# gigafoc.net
KiCad netlist of a schematic drawn in EAGLE
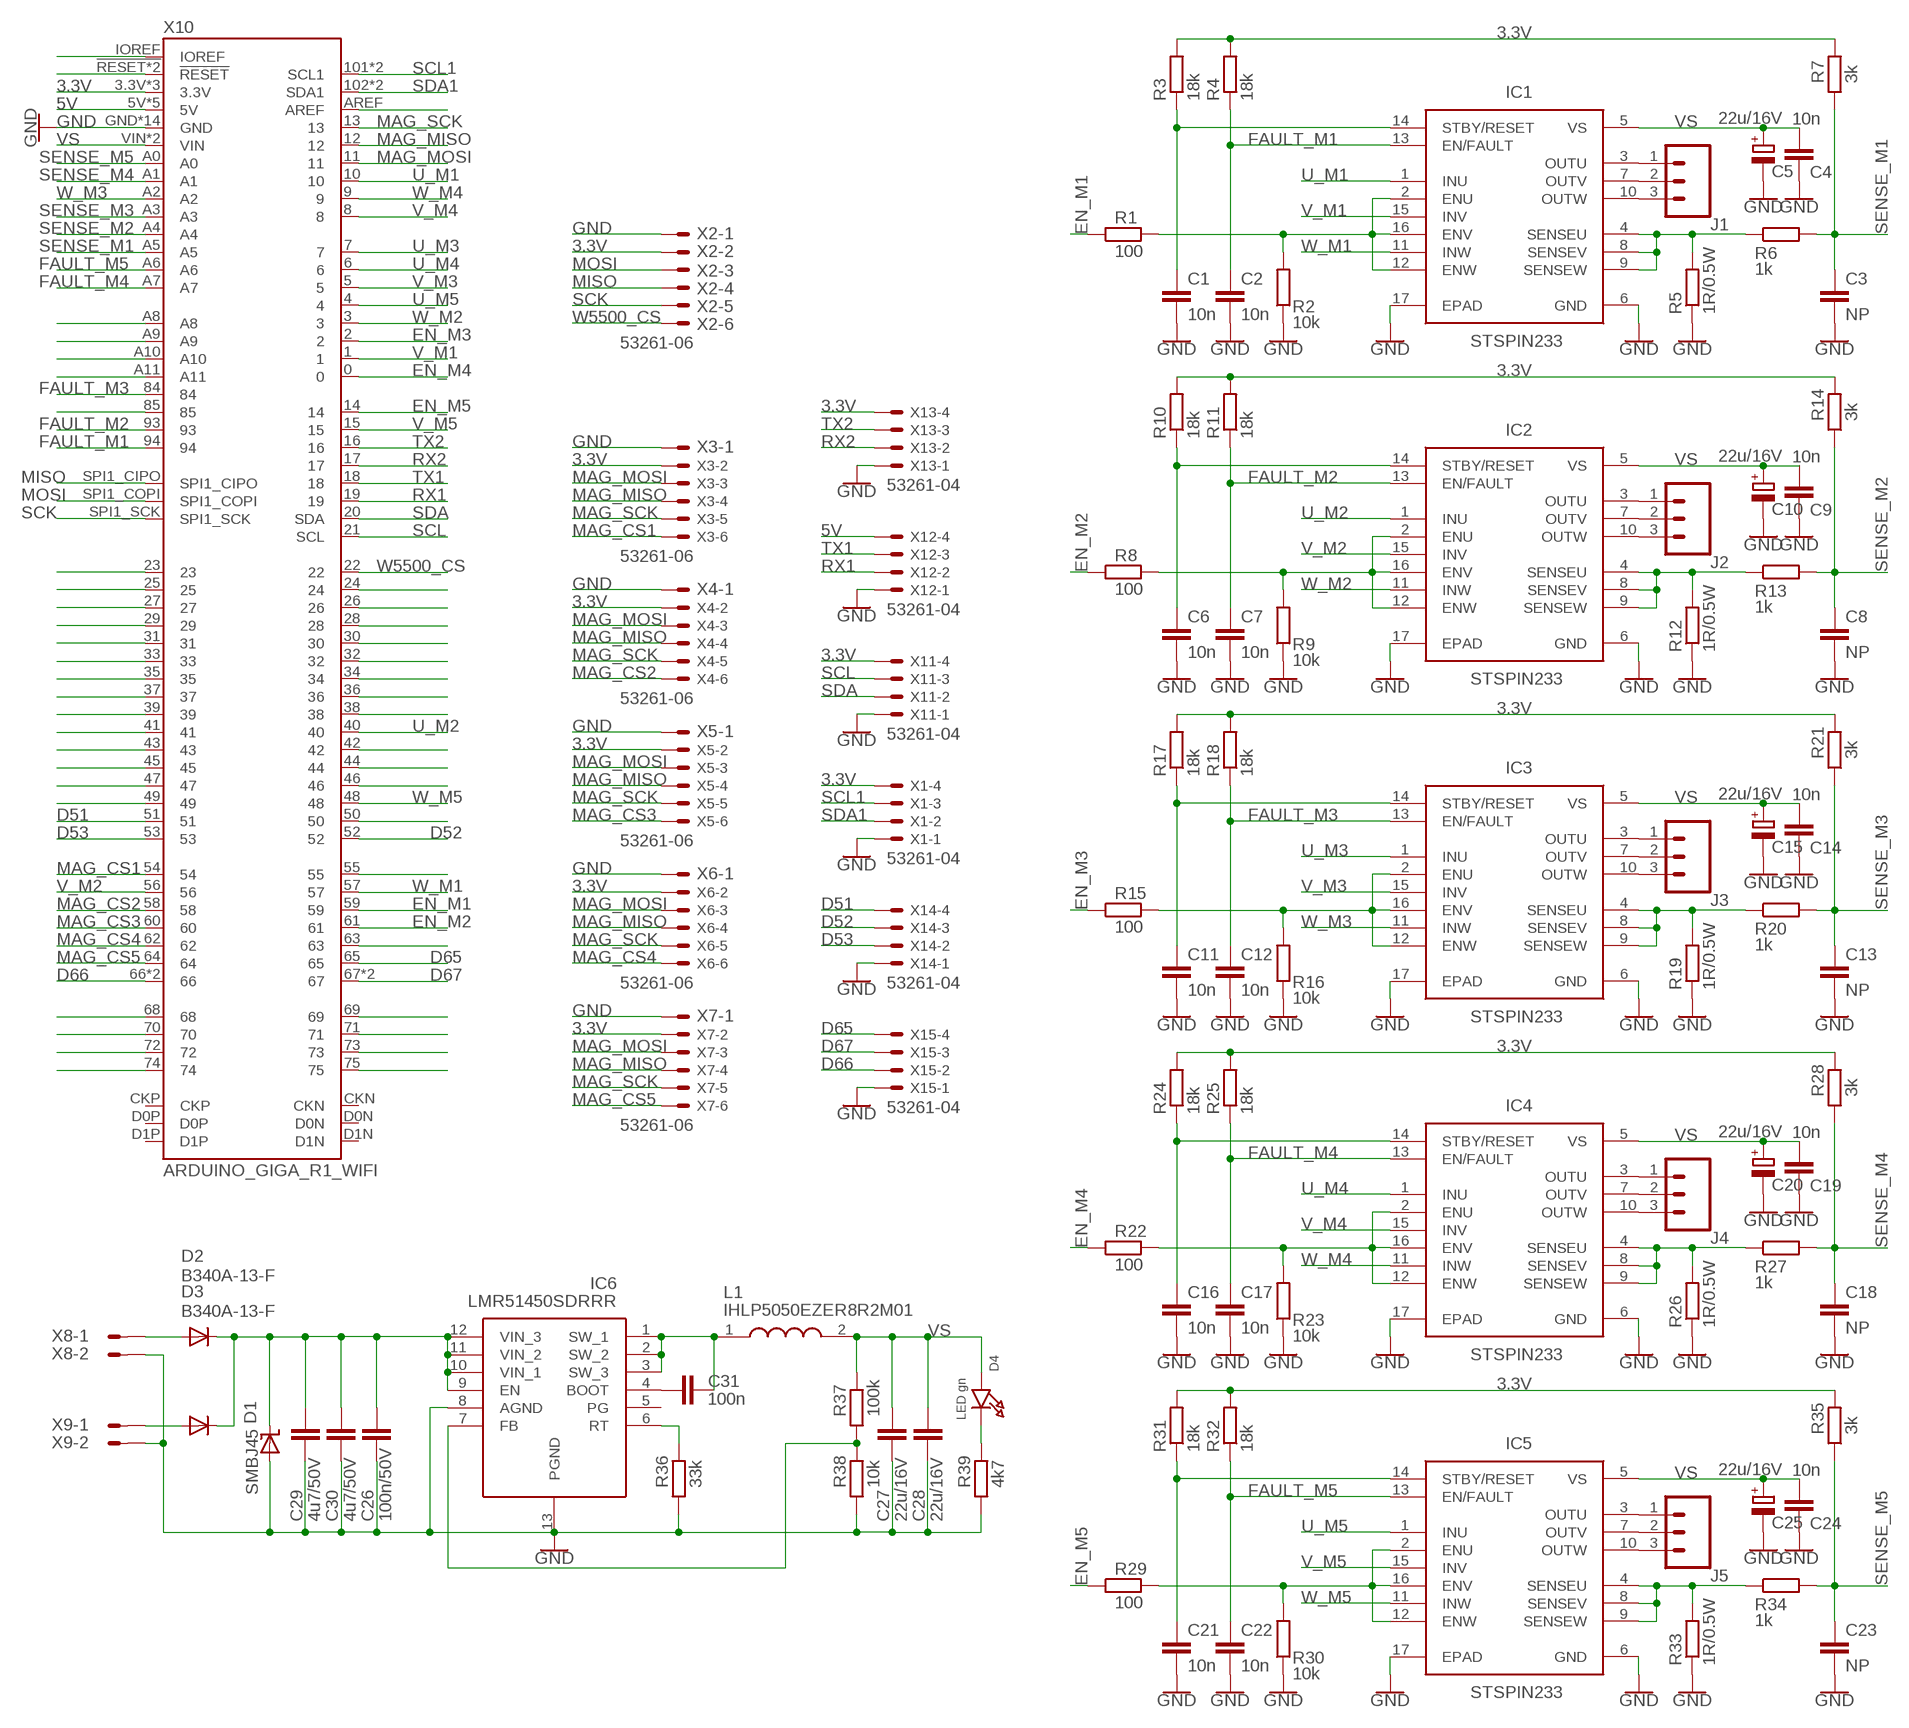
[diagram p0: schematic, sheet 1]

(export (version "E")
  (design (tool "Eeschema 10.0.6"))
  (components
    (comp (ref "C1")
      (value "10n")
      (footprint "eagle-import:C0603")
      (libsource (lib "eagle-import") (part "C-EUC0603"))
    )
    (comp (ref "C2")
      (value "10n")
      (footprint "eagle-import:C0603")
      (libsource (lib "eagle-import") (part "C-EUC0603"))
    )
    (comp (ref "C3")
      (value "NP")
      (footprint "eagle-import:C0603")
      (libsource (lib "eagle-import") (part "C-EUC0603"))
    )
    (comp (ref "C4")
      (value "10n")
      (footprint "eagle-import:C0603")
      (libsource (lib "eagle-import") (part "C-EUC0603"))
    )
    (comp (ref "C5")
      (value "22u/16V")
      (footprint "eagle-import:SMC_B")
      (libsource (lib "eagle-import") (part "CPOL-EUSMCB"))
    )
    (comp (ref "C6")
      (value "10n")
      (footprint "eagle-import:C0603")
      (libsource (lib "eagle-import") (part "C-EUC0603"))
    )
    (comp (ref "C7")
      (value "10n")
      (footprint "eagle-import:C0603")
      (libsource (lib "eagle-import") (part "C-EUC0603"))
    )
    (comp (ref "C8")
      (value "NP")
      (footprint "eagle-import:C0603")
      (libsource (lib "eagle-import") (part "C-EUC0603"))
    )
    (comp (ref "C9")
      (value "10n")
      (footprint "eagle-import:C0603")
      (libsource (lib "eagle-import") (part "C-EUC0603"))
    )
    (comp (ref "C10")
      (value "22u/16V")
      (footprint "eagle-import:SMC_B")
      (libsource (lib "eagle-import") (part "CPOL-EUSMCB"))
    )
    (comp (ref "C11")
      (value "10n")
      (footprint "eagle-import:C0603")
      (libsource (lib "eagle-import") (part "C-EUC0603"))
    )
    (comp (ref "C12")
      (value "10n")
      (footprint "eagle-import:C0603")
      (libsource (lib "eagle-import") (part "C-EUC0603"))
    )
    (comp (ref "C13")
      (value "NP")
      (footprint "eagle-import:C0603")
      (libsource (lib "eagle-import") (part "C-EUC0603"))
    )
    (comp (ref "C14")
      (value "10n")
      (footprint "eagle-import:C0603")
      (libsource (lib "eagle-import") (part "C-EUC0603"))
    )
    (comp (ref "C15")
      (value "22u/16V")
      (footprint "eagle-import:SMC_B")
      (libsource (lib "eagle-import") (part "CPOL-EUSMCB"))
    )
    (comp (ref "C16")
      (value "10n")
      (footprint "eagle-import:C0603")
      (libsource (lib "eagle-import") (part "C-EUC0603"))
    )
    (comp (ref "C17")
      (value "10n")
      (footprint "eagle-import:C0603")
      (libsource (lib "eagle-import") (part "C-EUC0603"))
    )
    (comp (ref "C18")
      (value "NP")
      (footprint "eagle-import:C0603")
      (libsource (lib "eagle-import") (part "C-EUC0603"))
    )
    (comp (ref "C19")
      (value "10n")
      (footprint "eagle-import:C0603")
      (libsource (lib "eagle-import") (part "C-EUC0603"))
    )
    (comp (ref "C20")
      (value "22u/16V")
      (footprint "eagle-import:SMC_B")
      (libsource (lib "eagle-import") (part "CPOL-EUSMCB"))
    )
    (comp (ref "C21")
      (value "10n")
      (footprint "eagle-import:C0603")
      (libsource (lib "eagle-import") (part "C-EUC0603"))
    )
    (comp (ref "C22")
      (value "10n")
      (footprint "eagle-import:C0603")
      (libsource (lib "eagle-import") (part "C-EUC0603"))
    )
    (comp (ref "C23")
      (value "NP")
      (footprint "eagle-import:C0603")
      (libsource (lib "eagle-import") (part "C-EUC0603"))
    )
    (comp (ref "C24")
      (value "10n")
      (footprint "eagle-import:C0603")
      (libsource (lib "eagle-import") (part "C-EUC0603"))
    )
    (comp (ref "C25")
      (value "22u/16V")
      (footprint "eagle-import:SMC_B")
      (libsource (lib "eagle-import") (part "CPOL-EUSMCB"))
    )
    (comp (ref "C26")
      (value "100n/50V")
      (footprint "eagle-import:C0805")
      (libsource (lib "eagle-import") (part "C-EUC0805"))
    )
    (comp (ref "C27")
      (value "22u/16V")
      (footprint "eagle-import:C1210")
      (libsource (lib "eagle-import") (part "C-EUC1210"))
    )
    (comp (ref "C28")
      (value "22u/16V")
      (footprint "eagle-import:C1210")
      (libsource (lib "eagle-import") (part "C-EUC1210"))
    )
    (comp (ref "C29")
      (value "4u7/50V")
      (footprint "eagle-import:C1210K")
      (libsource (lib "eagle-import") (part "C-EUC1210K"))
    )
    (comp (ref "C30")
      (value "4u7/50V")
      (footprint "eagle-import:C1210K")
      (libsource (lib "eagle-import") (part "C-EUC1210K"))
    )
    (comp (ref "C31")
      (value "100n")
      (footprint "eagle-import:C0603")
      (libsource (lib "eagle-import") (part "C-EUC0603"))
    )
    (comp (ref "D1")
      (value "SMBJ45")
      (footprint "eagle-import:SMBJ")
      (libsource (lib "eagle-import") (part "SUPPRESSOR-SMBJ"))
    )
    (comp (ref "D2")
      (value "B340A-13-F")
      (footprint "eagle-import:DO214AC")
      (libsource (lib "eagle-import") (part "DIODE-DO214AC"))
    )
    (comp (ref "D3")
      (value "B340A-13-F")
      (footprint "eagle-import:DO214AC")
      (libsource (lib "eagle-import") (part "DIODE-DO214AC"))
    )
    (comp (ref "D4")
      (value "LED gn")
      (footprint "eagle-import:CHIPLED_0603_NOOUTLINE")
      (libsource (lib "eagle-import") (part "LED0603_NOOUTLINE"))
    )
    (comp (ref "IC1")
      (value "STSPIN233")
      (footprint "eagle-import:QFN50P300X300X100-17N")
      (fields (field (name "MOUSER_PART_NUMBER") "511-STSPIN233"))
      (libsource (lib "eagle-import") (part "STSPIN233"))
    )
    (comp (ref "IC2")
      (value "STSPIN233")
      (footprint "eagle-import:QFN50P300X300X100-17N")
      (fields (field (name "MOUSER_PART_NUMBER") "511-STSPIN233"))
      (libsource (lib "eagle-import") (part "STSPIN233"))
    )
    (comp (ref "IC3")
      (value "STSPIN233")
      (footprint "eagle-import:QFN50P300X300X100-17N")
      (fields (field (name "MOUSER_PART_NUMBER") "511-STSPIN233"))
      (libsource (lib "eagle-import") (part "STSPIN233"))
    )
    (comp (ref "IC4")
      (value "STSPIN233")
      (footprint "eagle-import:QFN50P300X300X100-17N")
      (fields (field (name "MOUSER_PART_NUMBER") "511-STSPIN233"))
      (libsource (lib "eagle-import") (part "STSPIN233"))
    )
    (comp (ref "IC5")
      (value "STSPIN233")
      (footprint "eagle-import:QFN50P300X300X100-17N")
      (fields (field (name "MOUSER_PART_NUMBER") "511-STSPIN233"))
      (libsource (lib "eagle-import") (part "STSPIN233"))
    )
    (comp (ref "IC6")
      (value "LMR51450SDRRR")
      (footprint "eagle-import:SON50P300X300X80-13N")
      (fields (field (name "MOUSER_PART_NUMBER") "595-LMR51450SDRRR"))
      (libsource (lib "eagle-import") (part "LMR51450SDRRR"))
    )
    (comp (ref "J1")
      (value "CONN_03POLAR")
      (footprint "eagle-import:MOLEX-1X3")
      (libsource (lib "eagle-import") (part "CONN_03POLAR"))
    )
    (comp (ref "J2")
      (value "CONN_03POLAR")
      (footprint "eagle-import:MOLEX-1X3")
      (libsource (lib "eagle-import") (part "CONN_03POLAR"))
    )
    (comp (ref "J3")
      (value "CONN_03POLAR")
      (footprint "eagle-import:MOLEX-1X3")
      (libsource (lib "eagle-import") (part "CONN_03POLAR"))
    )
    (comp (ref "J4")
      (value "CONN_03POLAR")
      (footprint "eagle-import:MOLEX-1X3")
      (libsource (lib "eagle-import") (part "CONN_03POLAR"))
    )
    (comp (ref "J5")
      (value "CONN_03POLAR")
      (footprint "eagle-import:MOLEX-1X3")
      (libsource (lib "eagle-import") (part "CONN_03POLAR"))
    )
    (comp (ref "L1")
      (value "IHLP5050EZER8R2M01")
      (footprint "eagle-import:INDPM132129X500N")
      (fields (field (name "MOUSER_PART_NUMBER") "70-IHLP5050EZER8R2M1"))
      (libsource (lib "eagle-import") (part "IHLP5050EZER8R2M01"))
    )
    (comp (ref "R1")
      (value "100")
      (footprint "eagle-import:R0603")
      (libsource (lib "eagle-import") (part "R-EU_R0603"))
    )
    (comp (ref "R2")
      (value "10k")
      (footprint "eagle-import:R0603")
      (libsource (lib "eagle-import") (part "R-EU_R0603"))
    )
    (comp (ref "R3")
      (value "18k")
      (footprint "eagle-import:R0603")
      (libsource (lib "eagle-import") (part "R-EU_R0603"))
    )
    (comp (ref "R4")
      (value "18k")
      (footprint "eagle-import:R0603")
      (libsource (lib "eagle-import") (part "R-EU_R0603"))
    )
    (comp (ref "R5")
      (value "1R/0.5W")
      (footprint "eagle-import:R1206")
      (libsource (lib "eagle-import") (part "R-EU_R1206"))
    )
    (comp (ref "R6")
      (value "1k")
      (footprint "eagle-import:R0603")
      (libsource (lib "eagle-import") (part "R-EU_R0603"))
    )
    (comp (ref "R7")
      (value "3k")
      (footprint "eagle-import:R0603")
      (libsource (lib "eagle-import") (part "R-EU_R0603"))
    )
    (comp (ref "R8")
      (value "100")
      (footprint "eagle-import:R0603")
      (libsource (lib "eagle-import") (part "R-EU_R0603"))
    )
    (comp (ref "R9")
      (value "10k")
      (footprint "eagle-import:R0603")
      (libsource (lib "eagle-import") (part "R-EU_R0603"))
    )
    (comp (ref "R10")
      (value "18k")
      (footprint "eagle-import:R0603")
      (libsource (lib "eagle-import") (part "R-EU_R0603"))
    )
    (comp (ref "R11")
      (value "18k")
      (footprint "eagle-import:R0603")
      (libsource (lib "eagle-import") (part "R-EU_R0603"))
    )
    (comp (ref "R12")
      (value "1R/0.5W")
      (footprint "eagle-import:R1206")
      (libsource (lib "eagle-import") (part "R-EU_R1206"))
    )
    (comp (ref "R13")
      (value "1k")
      (footprint "eagle-import:R0603")
      (libsource (lib "eagle-import") (part "R-EU_R0603"))
    )
    (comp (ref "R14")
      (value "3k")
      (footprint "eagle-import:R0603")
      (libsource (lib "eagle-import") (part "R-EU_R0603"))
    )
    (comp (ref "R15")
      (value "100")
      (footprint "eagle-import:R0603")
      (libsource (lib "eagle-import") (part "R-EU_R0603"))
    )
    (comp (ref "R16")
      (value "10k")
      (footprint "eagle-import:R0603")
      (libsource (lib "eagle-import") (part "R-EU_R0603"))
    )
    (comp (ref "R17")
      (value "18k")
      (footprint "eagle-import:R0603")
      (libsource (lib "eagle-import") (part "R-EU_R0603"))
    )
    (comp (ref "R18")
      (value "18k")
      (footprint "eagle-import:R0603")
      (libsource (lib "eagle-import") (part "R-EU_R0603"))
    )
    (comp (ref "R19")
      (value "1R/0.5W")
      (footprint "eagle-import:R1206")
      (libsource (lib "eagle-import") (part "R-EU_R1206"))
    )
    (comp (ref "R20")
      (value "1k")
      (footprint "eagle-import:R0603")
      (libsource (lib "eagle-import") (part "R-EU_R0603"))
    )
    (comp (ref "R21")
      (value "3k")
      (footprint "eagle-import:R0603")
      (libsource (lib "eagle-import") (part "R-EU_R0603"))
    )
    (comp (ref "R22")
      (value "100")
      (footprint "eagle-import:R0603")
      (libsource (lib "eagle-import") (part "R-EU_R0603"))
    )
    (comp (ref "R23")
      (value "10k")
      (footprint "eagle-import:R0603")
      (libsource (lib "eagle-import") (part "R-EU_R0603"))
    )
    (comp (ref "R24")
      (value "18k")
      (footprint "eagle-import:R0603")
      (libsource (lib "eagle-import") (part "R-EU_R0603"))
    )
    (comp (ref "R25")
      (value "18k")
      (footprint "eagle-import:R0603")
      (libsource (lib "eagle-import") (part "R-EU_R0603"))
    )
    (comp (ref "R26")
      (value "1R/0.5W")
      (footprint "eagle-import:R1206")
      (libsource (lib "eagle-import") (part "R-EU_R1206"))
    )
    (comp (ref "R27")
      (value "1k")
      (footprint "eagle-import:R0603")
      (libsource (lib "eagle-import") (part "R-EU_R0603"))
    )
    (comp (ref "R28")
      (value "3k")
      (footprint "eagle-import:R0603")
      (libsource (lib "eagle-import") (part "R-EU_R0603"))
    )
    (comp (ref "R29")
      (value "100")
      (footprint "eagle-import:R0603")
      (libsource (lib "eagle-import") (part "R-EU_R0603"))
    )
    (comp (ref "R30")
      (value "10k")
      (footprint "eagle-import:R0603")
      (libsource (lib "eagle-import") (part "R-EU_R0603"))
    )
    (comp (ref "R31")
      (value "18k")
      (footprint "eagle-import:R0603")
      (libsource (lib "eagle-import") (part "R-EU_R0603"))
    )
    (comp (ref "R32")
      (value "18k")
      (footprint "eagle-import:R0603")
      (libsource (lib "eagle-import") (part "R-EU_R0603"))
    )
    (comp (ref "R33")
      (value "1R/0.5W")
      (footprint "eagle-import:R1206")
      (libsource (lib "eagle-import") (part "R-EU_R1206"))
    )
    (comp (ref "R34")
      (value "1k")
      (footprint "eagle-import:R0603")
      (libsource (lib "eagle-import") (part "R-EU_R0603"))
    )
    (comp (ref "R35")
      (value "3k")
      (footprint "eagle-import:R0603")
      (libsource (lib "eagle-import") (part "R-EU_R0603"))
    )
    (comp (ref "R36")
      (value "33k")
      (footprint "eagle-import:R0603")
      (libsource (lib "eagle-import") (part "R-EU_R0603"))
    )
    (comp (ref "R37")
      (value "100k")
      (footprint "eagle-import:R0603")
      (libsource (lib "eagle-import") (part "R-EU_R0603"))
    )
    (comp (ref "R38")
      (value "10k")
      (footprint "eagle-import:R0603")
      (libsource (lib "eagle-import") (part "R-EU_R0603"))
    )
    (comp (ref "R39")
      (value "4k7")
      (footprint "eagle-import:R0603")
      (libsource (lib "eagle-import") (part "R-EU_R0603"))
    )
    (comp (ref "X1")
      (value "53261-04")
      (footprint "eagle-import:53261-04")
      (fields (field (name "MF") "MOLEX"))
      (libsource (lib "eagle-import") (part "53?-04261"))
    )
    (comp (ref "X2")
      (value "53261-06")
      (footprint "eagle-import:53261-06")
      (fields (field (name "MF") "MOLEX"))
      (libsource (lib "eagle-import") (part "53?-06261"))
    )
    (comp (ref "X3")
      (value "53261-06")
      (footprint "eagle-import:53261-06")
      (fields (field (name "MF") "MOLEX"))
      (libsource (lib "eagle-import") (part "53?-06261"))
    )
    (comp (ref "X4")
      (value "53261-06")
      (footprint "eagle-import:53261-06")
      (fields (field (name "MF") "MOLEX"))
      (libsource (lib "eagle-import") (part "53?-06261"))
    )
    (comp (ref "X5")
      (value "53261-06")
      (footprint "eagle-import:53261-06")
      (fields (field (name "MF") "MOLEX"))
      (libsource (lib "eagle-import") (part "53?-06261"))
    )
    (comp (ref "X6")
      (value "53261-06")
      (footprint "eagle-import:53261-06")
      (fields (field (name "MF") "MOLEX"))
      (libsource (lib "eagle-import") (part "53?-06261"))
    )
    (comp (ref "X7")
      (value "53261-06")
      (footprint "eagle-import:53261-06")
      (fields (field (name "MF") "MOLEX"))
      (libsource (lib "eagle-import") (part "53?-06261"))
    )
    (comp (ref "X8")
      (value "S02P")
      (footprint "eagle-import:S02P")
      (libsource (lib "eagle-import") (part "S02P"))
    )
    (comp (ref "X9")
      (value "S02P")
      (footprint "eagle-import:S02P")
      (libsource (lib "eagle-import") (part "S02P"))
    )
    (comp (ref "X10")
      (value "ARDUINO_GIGA_R1_WIFI")
      (footprint "eagle-import:ARDUINO_GIGA_NO_SILK")
      (libsource (lib "eagle-import") (part "ARDUINO_GIGA_R1_WIFI"))
    )
    (comp (ref "X11")
      (value "53261-04")
      (footprint "eagle-import:53261-04")
      (fields (field (name "MF") "MOLEX"))
      (libsource (lib "eagle-import") (part "53?-04261"))
    )
    (comp (ref "X12")
      (value "53261-04")
      (footprint "eagle-import:53261-04")
      (fields (field (name "MF") "MOLEX"))
      (libsource (lib "eagle-import") (part "53?-04261"))
    )
    (comp (ref "X13")
      (value "53261-04")
      (footprint "eagle-import:53261-04")
      (fields (field (name "MF") "MOLEX"))
      (libsource (lib "eagle-import") (part "53?-04261"))
    )
    (comp (ref "X14")
      (value "53261-04")
      (footprint "eagle-import:53261-04")
      (fields (field (name "MF") "MOLEX"))
      (libsource (lib "eagle-import") (part "53?-04261"))
    )
    (comp (ref "X15")
      (value "53261-04")
      (footprint "eagle-import:53261-04")
      (fields (field (name "MF") "MOLEX"))
      (libsource (lib "eagle-import") (part "53?-04261"))
    )
  )
  (nets
    (net (code "1") (name "/3.3V") (class "Default")
      (node (ref "R10") (pin "2") (pinfunction "2_2") (pintype "passive"))
      (node (ref "R11") (pin "2") (pinfunction "2_2") (pintype "passive"))
      (node (ref "R14") (pin "2") (pinfunction "2_2") (pintype "passive"))
      (node (ref "R17") (pin "2") (pinfunction "2_2") (pintype "passive"))
      (node (ref "R18") (pin "2") (pinfunction "2_2") (pintype "passive"))
      (node (ref "R21") (pin "2") (pinfunction "2_2") (pintype "passive"))
      (node (ref "R24") (pin "2") (pinfunction "2_2") (pintype "passive"))
      (node (ref "R25") (pin "2") (pinfunction "2_2") (pintype "passive"))
      (node (ref "R28") (pin "2") (pinfunction "2_2") (pintype "passive"))
      (node (ref "R3") (pin "2") (pinfunction "2_2") (pintype "passive"))
      (node (ref "R31") (pin "2") (pinfunction "2_2") (pintype "passive"))
      (node (ref "R32") (pin "2") (pinfunction "2_2") (pintype "passive"))
      (node (ref "R35") (pin "2") (pinfunction "2_2") (pintype "passive"))
      (node (ref "R4") (pin "2") (pinfunction "2_2") (pintype "passive"))
      (node (ref "R7") (pin "2") (pinfunction "2_2") (pintype "passive"))
      (node (ref "X1") (pin "4") (pinfunction "S_4") (pintype "passive"))
      (node (ref "X10") (pin "3.3V") (pinfunction "3.3V_3.3V") (pintype "bidirectional"))
      (node (ref "X10") (pin "3.3V@1") (pinfunction "3.3V_3.3V@1") (pintype "bidirectional"))
      (node (ref "X10") (pin "3.3V@2") (pinfunction "3.3V_3.3V@2") (pintype "bidirectional"))
      (node (ref "X11") (pin "4") (pinfunction "S_4") (pintype "passive"))
      (node (ref "X13") (pin "4") (pinfunction "S_4") (pintype "passive"))
      (node (ref "X2") (pin "2") (pinfunction "S_2") (pintype "passive"))
      (node (ref "X3") (pin "2") (pinfunction "S_2") (pintype "passive"))
      (node (ref "X4") (pin "2") (pinfunction "S_2") (pintype "passive"))
      (node (ref "X5") (pin "2") (pinfunction "S_2") (pintype "passive"))
      (node (ref "X6") (pin "2") (pinfunction "S_2") (pintype "passive"))
      (node (ref "X7") (pin "2") (pinfunction "S_2") (pintype "passive"))
    )
    (net (code "2") (name "/5V") (class "Default")
      (node (ref "X10") (pin "5V") (pinfunction "5V_5V") (pintype "bidirectional"))
      (node (ref "X10") (pin "5V@1") (pinfunction "5V_5V@1") (pintype "bidirectional"))
      (node (ref "X10") (pin "5V@2") (pinfunction "5V_5V@2") (pintype "bidirectional"))
      (node (ref "X10") (pin "5V@3") (pinfunction "5V_5V@3") (pintype "bidirectional"))
      (node (ref "X10") (pin "5V@4") (pinfunction "5V_5V@4") (pintype "bidirectional"))
      (node (ref "X12") (pin "4") (pinfunction "S_4") (pintype "passive"))
    )
    (net (code "3") (name "/D51") (class "Default")
      (node (ref "X10") (pin "51") (pinfunction "51_51") (pintype "bidirectional"))
      (node (ref "X14") (pin "4") (pinfunction "S_4") (pintype "passive"))
    )
    (net (code "4") (name "/D52") (class "Default")
      (node (ref "X10") (pin "52") (pinfunction "52_52") (pintype "bidirectional"))
      (node (ref "X14") (pin "3") (pinfunction "S_3") (pintype "passive"))
    )
    (net (code "5") (name "/D53") (class "Default")
      (node (ref "X10") (pin "53") (pinfunction "53_53") (pintype "bidirectional"))
      (node (ref "X14") (pin "2") (pinfunction "S_2") (pintype "passive"))
    )
    (net (code "6") (name "/D65") (class "Default")
      (node (ref "X10") (pin "65") (pinfunction "65_65") (pintype "bidirectional"))
      (node (ref "X15") (pin "4") (pinfunction "S_4") (pintype "passive"))
    )
    (net (code "7") (name "/D66") (class "Default")
      (node (ref "X10") (pin "66") (pinfunction "66_66") (pintype "bidirectional"))
      (node (ref "X10") (pin "66@1") (pinfunction "66_66@1") (pintype "bidirectional"))
      (node (ref "X15") (pin "2") (pinfunction "S_2") (pintype "passive"))
    )
    (net (code "8") (name "/D67") (class "Default")
      (node (ref "X10") (pin "67") (pinfunction "67_67") (pintype "bidirectional"))
      (node (ref "X10") (pin "67@1") (pinfunction "67_67@1") (pintype "bidirectional"))
      (node (ref "X15") (pin "3") (pinfunction "S_3") (pintype "passive"))
    )
    (net (code "9") (name "/EN_M1") (class "Default")
      (node (ref "R1") (pin "1") (pinfunction "1_1") (pintype "passive"))
      (node (ref "X10") (pin "59") (pinfunction "59_59") (pintype "bidirectional"))
    )
    (net (code "10") (name "/EN_M2") (class "Default")
      (node (ref "R8") (pin "1") (pinfunction "1_1") (pintype "passive"))
      (node (ref "X10") (pin "61") (pinfunction "61_61") (pintype "bidirectional"))
    )
    (net (code "11") (name "/EN_M3") (class "Default")
      (node (ref "R15") (pin "1") (pinfunction "1_1") (pintype "passive"))
      (node (ref "X10") (pin "2") (pinfunction "2_2") (pintype "bidirectional"))
    )
    (net (code "12") (name "/EN_M4") (class "Default")
      (node (ref "R22") (pin "1") (pinfunction "1_1") (pintype "passive"))
      (node (ref "X10") (pin "0") (pinfunction "0_0") (pintype "bidirectional"))
    )
    (net (code "13") (name "/EN_M5") (class "Default")
      (node (ref "R29") (pin "1") (pinfunction "1_1") (pintype "passive"))
      (node (ref "X10") (pin "14") (pinfunction "14_14") (pintype "bidirectional"))
    )
    (net (code "14") (name "/FAULT_M1") (class "Default")
      (node (ref "C2") (pin "2") (pinfunction "2_2") (pintype "passive"))
      (node (ref "IC1") (pin "13") (pinfunction "EN/FAULT_13") (pintype "bidirectional"))
      (node (ref "R4") (pin "1") (pinfunction "1_1") (pintype "passive"))
      (node (ref "X10") (pin "94") (pinfunction "94_94") (pintype "bidirectional"))
    )
    (net (code "15") (name "/FAULT_M2") (class "Default")
      (node (ref "C7") (pin "2") (pinfunction "2_2") (pintype "passive"))
      (node (ref "IC2") (pin "13") (pinfunction "EN/FAULT_13") (pintype "bidirectional"))
      (node (ref "R11") (pin "1") (pinfunction "1_1") (pintype "passive"))
      (node (ref "X10") (pin "93") (pinfunction "93_93") (pintype "bidirectional"))
    )
    (net (code "16") (name "/FAULT_M3") (class "Default")
      (node (ref "C12") (pin "2") (pinfunction "2_2") (pintype "passive"))
      (node (ref "IC3") (pin "13") (pinfunction "EN/FAULT_13") (pintype "bidirectional"))
      (node (ref "R18") (pin "1") (pinfunction "1_1") (pintype "passive"))
      (node (ref "X10") (pin "84") (pinfunction "84_84") (pintype "bidirectional"))
    )
    (net (code "17") (name "/FAULT_M4") (class "Default")
      (node (ref "C17") (pin "2") (pinfunction "2_2") (pintype "passive"))
      (node (ref "IC4") (pin "13") (pinfunction "EN/FAULT_13") (pintype "bidirectional"))
      (node (ref "R25") (pin "1") (pinfunction "1_1") (pintype "passive"))
      (node (ref "X10") (pin "A7") (pinfunction "A7_A7") (pintype "bidirectional"))
    )
    (net (code "18") (name "/FAULT_M5") (class "Default")
      (node (ref "C22") (pin "2") (pinfunction "2_2") (pintype "passive"))
      (node (ref "IC5") (pin "13") (pinfunction "EN/FAULT_13") (pintype "bidirectional"))
      (node (ref "R32") (pin "1") (pinfunction "1_1") (pintype "passive"))
      (node (ref "X10") (pin "A6") (pinfunction "A6_A6") (pintype "bidirectional"))
    )
    (net (code "19") (name "/MAG_CS1") (class "Default")
      (node (ref "X10") (pin "54") (pinfunction "54_54") (pintype "bidirectional"))
      (node (ref "X3") (pin "6") (pinfunction "S_6") (pintype "passive"))
    )
    (net (code "20") (name "/MAG_CS2") (class "Default")
      (node (ref "X10") (pin "58") (pinfunction "58_58") (pintype "bidirectional"))
      (node (ref "X4") (pin "6") (pinfunction "S_6") (pintype "passive"))
    )
    (net (code "21") (name "/MAG_CS3") (class "Default")
      (node (ref "X10") (pin "60") (pinfunction "60_60") (pintype "bidirectional"))
      (node (ref "X5") (pin "6") (pinfunction "S_6") (pintype "passive"))
    )
    (net (code "22") (name "/MAG_CS4") (class "Default")
      (node (ref "X10") (pin "62") (pinfunction "62_62") (pintype "bidirectional"))
      (node (ref "X6") (pin "6") (pinfunction "S_6") (pintype "passive"))
    )
    (net (code "23") (name "/MAG_CS5") (class "Default")
      (node (ref "X10") (pin "64") (pinfunction "64_64") (pintype "bidirectional"))
      (node (ref "X7") (pin "6") (pinfunction "S_6") (pintype "passive"))
    )
    (net (code "24") (name "/MAG_MISO") (class "Default")
      (node (ref "X10") (pin "12") (pinfunction "12_12") (pintype "bidirectional"))
      (node (ref "X3") (pin "4") (pinfunction "S_4") (pintype "passive"))
      (node (ref "X4") (pin "4") (pinfunction "S_4") (pintype "passive"))
      (node (ref "X5") (pin "4") (pinfunction "S_4") (pintype "passive"))
      (node (ref "X6") (pin "4") (pinfunction "S_4") (pintype "passive"))
      (node (ref "X7") (pin "4") (pinfunction "S_4") (pintype "passive"))
    )
    (net (code "25") (name "/MAG_MOSI") (class "Default")
      (node (ref "X10") (pin "11") (pinfunction "11_11") (pintype "bidirectional"))
      (node (ref "X3") (pin "3") (pinfunction "S_3") (pintype "passive"))
      (node (ref "X4") (pin "3") (pinfunction "S_3") (pintype "passive"))
      (node (ref "X5") (pin "3") (pinfunction "S_3") (pintype "passive"))
      (node (ref "X6") (pin "3") (pinfunction "S_3") (pintype "passive"))
      (node (ref "X7") (pin "3") (pinfunction "S_3") (pintype "passive"))
    )
    (net (code "26") (name "/MAG_SCK") (class "Default")
      (node (ref "X10") (pin "13") (pinfunction "13_13") (pintype "bidirectional"))
      (node (ref "X3") (pin "5") (pinfunction "S_5") (pintype "passive"))
      (node (ref "X4") (pin "5") (pinfunction "S_5") (pintype "passive"))
      (node (ref "X5") (pin "5") (pinfunction "S_5") (pintype "passive"))
      (node (ref "X6") (pin "5") (pinfunction "S_5") (pintype "passive"))
      (node (ref "X7") (pin "5") (pinfunction "S_5") (pintype "passive"))
    )
    (net (code "27") (name "/MISO") (class "Default")
      (node (ref "X10") (pin "SPI1_CIPO") (pinfunction "SPI1_CIPO_SPI1_CIPO") (pintype "bidirectional"))
      (node (ref "X2") (pin "4") (pinfunction "S_4") (pintype "passive"))
    )
    (net (code "28") (name "/MOSI") (class "Default")
      (node (ref "X10") (pin "SPI1_COPI") (pinfunction "SPI1_COPI_SPI1_COPI") (pintype "bidirectional"))
      (node (ref "X2") (pin "3") (pinfunction "S_3") (pintype "passive"))
    )
    (net (code "29") (name "/RX1") (class "Default")
      (node (ref "X10") (pin "19") (pinfunction "19_19") (pintype "bidirectional"))
      (node (ref "X12") (pin "2") (pinfunction "S_2") (pintype "passive"))
    )
    (net (code "30") (name "/RX2") (class "Default")
      (node (ref "X10") (pin "17") (pinfunction "17_17") (pintype "bidirectional"))
      (node (ref "X13") (pin "2") (pinfunction "S_2") (pintype "passive"))
    )
    (net (code "31") (name "/SCK") (class "Default")
      (node (ref "X10") (pin "SPI1_SCK") (pinfunction "SPI1_SCK_SPI1_SCK") (pintype "bidirectional"))
      (node (ref "X2") (pin "5") (pinfunction "S_5") (pintype "passive"))
    )
    (net (code "32") (name "/SCL") (class "Default")
      (node (ref "X10") (pin "21") (pinfunction "SCL_21") (pintype "bidirectional"))
      (node (ref "X11") (pin "3") (pinfunction "S_3") (pintype "passive"))
    )
    (net (code "33") (name "/SCL1") (class "Default")
      (node (ref "X1") (pin "3") (pinfunction "S_3") (pintype "passive"))
      (node (ref "X10") (pin "101") (pinfunction "SCL1_101") (pintype "bidirectional"))
      (node (ref "X10") (pin "101@1") (pinfunction "SCL1_101@1") (pintype "bidirectional"))
    )
    (net (code "34") (name "/SDA") (class "Default")
      (node (ref "X10") (pin "20") (pinfunction "SDA_20") (pintype "bidirectional"))
      (node (ref "X11") (pin "2") (pinfunction "S_2") (pintype "passive"))
    )
    (net (code "35") (name "/SDA1") (class "Default")
      (node (ref "X1") (pin "2") (pinfunction "S_2") (pintype "passive"))
      (node (ref "X10") (pin "102") (pinfunction "SDA1_102") (pintype "bidirectional"))
      (node (ref "X10") (pin "102@1") (pinfunction "SDA1_102@1") (pintype "bidirectional"))
    )
    (net (code "36") (name "/SENSE_M1") (class "Default")
      (node (ref "C3") (pin "2") (pinfunction "2_2") (pintype "passive"))
      (node (ref "R6") (pin "2") (pinfunction "2_2") (pintype "passive"))
      (node (ref "R7") (pin "1") (pinfunction "1_1") (pintype "passive"))
      (node (ref "X10") (pin "A5") (pinfunction "A5_A5") (pintype "bidirectional"))
    )
    (net (code "37") (name "/SENSE_M2") (class "Default")
      (node (ref "C8") (pin "2") (pinfunction "2_2") (pintype "passive"))
      (node (ref "R13") (pin "2") (pinfunction "2_2") (pintype "passive"))
      (node (ref "R14") (pin "1") (pinfunction "1_1") (pintype "passive"))
      (node (ref "X10") (pin "A4") (pinfunction "A4_A4") (pintype "bidirectional"))
    )
    (net (code "38") (name "/SENSE_M3") (class "Default")
      (node (ref "C13") (pin "2") (pinfunction "2_2") (pintype "passive"))
      (node (ref "R20") (pin "2") (pinfunction "2_2") (pintype "passive"))
      (node (ref "R21") (pin "1") (pinfunction "1_1") (pintype "passive"))
      (node (ref "X10") (pin "A3") (pinfunction "A3_A3") (pintype "bidirectional"))
    )
    (net (code "39") (name "/SENSE_M4") (class "Default")
      (node (ref "C18") (pin "2") (pinfunction "2_2") (pintype "passive"))
      (node (ref "R27") (pin "2") (pinfunction "2_2") (pintype "passive"))
      (node (ref "R28") (pin "1") (pinfunction "1_1") (pintype "passive"))
      (node (ref "X10") (pin "A1") (pinfunction "A1_A1") (pintype "bidirectional"))
    )
    (net (code "40") (name "/SENSE_M5") (class "Default")
      (node (ref "C23") (pin "2") (pinfunction "2_2") (pintype "passive"))
      (node (ref "R34") (pin "2") (pinfunction "2_2") (pintype "passive"))
      (node (ref "R35") (pin "1") (pinfunction "1_1") (pintype "passive"))
      (node (ref "X10") (pin "A0") (pinfunction "A0_A0") (pintype "bidirectional"))
    )
    (net (code "41") (name "/TX1") (class "Default")
      (node (ref "X10") (pin "18") (pinfunction "18_18") (pintype "bidirectional"))
      (node (ref "X12") (pin "3") (pinfunction "S_3") (pintype "passive"))
    )
    (net (code "42") (name "/TX2") (class "Default")
      (node (ref "X10") (pin "16") (pinfunction "16_16") (pintype "bidirectional"))
      (node (ref "X13") (pin "3") (pinfunction "S_3") (pintype "passive"))
    )
    (net (code "43") (name "/U_M1") (class "Default")
      (node (ref "IC1") (pin "1") (pinfunction "INU_1") (pintype "bidirectional"))
      (node (ref "X10") (pin "10") (pinfunction "10_10") (pintype "bidirectional"))
    )
    (net (code "44") (name "/U_M2") (class "Default")
      (node (ref "IC2") (pin "1") (pinfunction "INU_1") (pintype "bidirectional"))
      (node (ref "X10") (pin "40") (pinfunction "40_40") (pintype "bidirectional"))
    )
    (net (code "45") (name "/U_M3") (class "Default")
      (node (ref "IC3") (pin "1") (pinfunction "INU_1") (pintype "bidirectional"))
      (node (ref "X10") (pin "7") (pinfunction "7_7") (pintype "bidirectional"))
    )
    (net (code "46") (name "/U_M4") (class "Default")
      (node (ref "IC4") (pin "1") (pinfunction "INU_1") (pintype "bidirectional"))
      (node (ref "X10") (pin "6") (pinfunction "6_6") (pintype "bidirectional"))
    )
    (net (code "47") (name "/U_M5") (class "Default")
      (node (ref "IC5") (pin "1") (pinfunction "INU_1") (pintype "bidirectional"))
      (node (ref "X10") (pin "4") (pinfunction "4_4") (pintype "bidirectional"))
    )
    (net (code "48") (name "/VS") (class "Default")
      (node (ref "C10") (pin "+") (pinfunction "+_+") (pintype "passive"))
      (node (ref "C14") (pin "2") (pinfunction "2_2") (pintype "passive"))
      (node (ref "C15") (pin "+") (pinfunction "+_+") (pintype "passive"))
      (node (ref "C19") (pin "2") (pinfunction "2_2") (pintype "passive"))
      (node (ref "C20") (pin "+") (pinfunction "+_+") (pintype "passive"))
      (node (ref "C24") (pin "2") (pinfunction "2_2") (pintype "passive"))
      (node (ref "C25") (pin "+") (pinfunction "+_+") (pintype "passive"))
      (node (ref "C27") (pin "1") (pinfunction "1_1") (pintype "passive"))
      (node (ref "C28") (pin "1") (pinfunction "1_1") (pintype "passive"))
      (node (ref "C4") (pin "2") (pinfunction "2_2") (pintype "passive"))
      (node (ref "C5") (pin "+") (pinfunction "+_+") (pintype "passive"))
      (node (ref "C9") (pin "2") (pinfunction "2_2") (pintype "passive"))
      (node (ref "D4") (pin "A") (pinfunction "A_A") (pintype "passive"))
      (node (ref "IC1") (pin "5") (pinfunction "VS_5") (pintype "bidirectional"))
      (node (ref "IC2") (pin "5") (pinfunction "VS_5") (pintype "bidirectional"))
      (node (ref "IC3") (pin "5") (pinfunction "VS_5") (pintype "bidirectional"))
      (node (ref "IC4") (pin "5") (pinfunction "VS_5") (pintype "bidirectional"))
      (node (ref "IC5") (pin "5") (pinfunction "VS_5") (pintype "bidirectional"))
      (node (ref "L1") (pin "2") (pinfunction "2_2") (pintype "bidirectional"))
      (node (ref "R37") (pin "2") (pinfunction "2_2") (pintype "passive"))
      (node (ref "X10") (pin "VIN") (pinfunction "VIN_VIN") (pintype "bidirectional"))
      (node (ref "X10") (pin "VIN@1") (pinfunction "VIN_VIN@1") (pintype "bidirectional"))
    )
    (net (code "49") (name "/V_M1") (class "Default")
      (node (ref "IC1") (pin "15") (pinfunction "INV_15") (pintype "bidirectional"))
      (node (ref "X10") (pin "1") (pinfunction "1_1") (pintype "bidirectional"))
    )
    (net (code "50") (name "/V_M2") (class "Default")
      (node (ref "IC2") (pin "15") (pinfunction "INV_15") (pintype "bidirectional"))
      (node (ref "X10") (pin "56") (pinfunction "56_56") (pintype "bidirectional"))
    )
    (net (code "51") (name "/V_M3") (class "Default")
      (node (ref "IC3") (pin "15") (pinfunction "INV_15") (pintype "bidirectional"))
      (node (ref "X10") (pin "5") (pinfunction "5_5") (pintype "bidirectional"))
    )
    (net (code "52") (name "/V_M4") (class "Default")
      (node (ref "IC4") (pin "15") (pinfunction "INV_15") (pintype "bidirectional"))
      (node (ref "X10") (pin "8") (pinfunction "8_8") (pintype "bidirectional"))
    )
    (net (code "53") (name "/V_M5") (class "Default")
      (node (ref "IC5") (pin "15") (pinfunction "INV_15") (pintype "bidirectional"))
      (node (ref "X10") (pin "15") (pinfunction "15_15") (pintype "bidirectional"))
    )
    (net (code "54") (name "/W5500_CS") (class "Default")
      (node (ref "X10") (pin "22") (pinfunction "22_22") (pintype "bidirectional"))
      (node (ref "X2") (pin "6") (pinfunction "S_6") (pintype "passive"))
    )
    (net (code "55") (name "/W_M1") (class "Default")
      (node (ref "IC1") (pin "11") (pinfunction "INW_11") (pintype "bidirectional"))
      (node (ref "X10") (pin "57") (pinfunction "57_57") (pintype "bidirectional"))
    )
    (net (code "56") (name "/W_M2") (class "Default")
      (node (ref "IC2") (pin "11") (pinfunction "INW_11") (pintype "bidirectional"))
      (node (ref "X10") (pin "3") (pinfunction "3_3") (pintype "bidirectional"))
    )
    (net (code "57") (name "/W_M3") (class "Default")
      (node (ref "IC3") (pin "11") (pinfunction "INW_11") (pintype "bidirectional"))
      (node (ref "X10") (pin "A2") (pinfunction "A2_A2") (pintype "bidirectional"))
    )
    (net (code "58") (name "/W_M4") (class "Default")
      (node (ref "IC4") (pin "11") (pinfunction "INW_11") (pintype "bidirectional"))
      (node (ref "X10") (pin "9") (pinfunction "9_9") (pintype "bidirectional"))
    )
    (net (code "59") (name "/W_M5") (class "Default")
      (node (ref "IC5") (pin "11") (pinfunction "INW_11") (pintype "bidirectional"))
      (node (ref "X10") (pin "48") (pinfunction "48_48") (pintype "bidirectional"))
    )
    (net (code "60") (name "GND") (class "Default")
      (node (ref "C1") (pin "1") (pinfunction "1_1") (pintype "passive"))
      (node (ref "C10") (pin "-") (pinfunction "-_-") (pintype "passive"))
      (node (ref "C11") (pin "1") (pinfunction "1_1") (pintype "passive"))
      (node (ref "C12") (pin "1") (pinfunction "1_1") (pintype "passive"))
      (node (ref "C13") (pin "1") (pinfunction "1_1") (pintype "passive"))
      (node (ref "C14") (pin "1") (pinfunction "1_1") (pintype "passive"))
      (node (ref "C15") (pin "-") (pinfunction "-_-") (pintype "passive"))
      (node (ref "C16") (pin "1") (pinfunction "1_1") (pintype "passive"))
      (node (ref "C17") (pin "1") (pinfunction "1_1") (pintype "passive"))
      (node (ref "C18") (pin "1") (pinfunction "1_1") (pintype "passive"))
      (node (ref "C19") (pin "1") (pinfunction "1_1") (pintype "passive"))
      (node (ref "C2") (pin "1") (pinfunction "1_1") (pintype "passive"))
      (node (ref "C20") (pin "-") (pinfunction "-_-") (pintype "passive"))
      (node (ref "C21") (pin "1") (pinfunction "1_1") (pintype "passive"))
      (node (ref "C22") (pin "1") (pinfunction "1_1") (pintype "passive"))
      (node (ref "C23") (pin "1") (pinfunction "1_1") (pintype "passive"))
      (node (ref "C24") (pin "1") (pinfunction "1_1") (pintype "passive"))
      (node (ref "C25") (pin "-") (pinfunction "-_-") (pintype "passive"))
      (node (ref "C26") (pin "2") (pinfunction "2_2") (pintype "passive"))
      (node (ref "C27") (pin "2") (pinfunction "2_2") (pintype "passive"))
      (node (ref "C28") (pin "2") (pinfunction "2_2") (pintype "passive"))
      (node (ref "C29") (pin "2") (pinfunction "2_2") (pintype "passive"))
      (node (ref "C3") (pin "1") (pinfunction "1_1") (pintype "passive"))
      (node (ref "C30") (pin "2") (pinfunction "2_2") (pintype "passive"))
      (node (ref "C4") (pin "1") (pinfunction "1_1") (pintype "passive"))
      (node (ref "C5") (pin "-") (pinfunction "-_-") (pintype "passive"))
      (node (ref "C6") (pin "1") (pinfunction "1_1") (pintype "passive"))
      (node (ref "C7") (pin "1") (pinfunction "1_1") (pintype "passive"))
      (node (ref "C8") (pin "1") (pinfunction "1_1") (pintype "passive"))
      (node (ref "C9") (pin "1") (pinfunction "1_1") (pintype "passive"))
      (node (ref "D1") (pin "A") (pinfunction "A_A") (pintype "passive"))
      (node (ref "IC1") (pin "17") (pinfunction "EPAD_17") (pintype "bidirectional"))
      (node (ref "IC1") (pin "6") (pinfunction "GND_6") (pintype "bidirectional"))
      (node (ref "IC2") (pin "17") (pinfunction "EPAD_17") (pintype "bidirectional"))
      (node (ref "IC2") (pin "6") (pinfunction "GND_6") (pintype "bidirectional"))
      (node (ref "IC3") (pin "17") (pinfunction "EPAD_17") (pintype "bidirectional"))
      (node (ref "IC3") (pin "6") (pinfunction "GND_6") (pintype "bidirectional"))
      (node (ref "IC4") (pin "17") (pinfunction "EPAD_17") (pintype "bidirectional"))
      (node (ref "IC4") (pin "6") (pinfunction "GND_6") (pintype "bidirectional"))
      (node (ref "IC5") (pin "17") (pinfunction "EPAD_17") (pintype "bidirectional"))
      (node (ref "IC5") (pin "6") (pinfunction "GND_6") (pintype "bidirectional"))
      (node (ref "IC6") (pin "13") (pinfunction "PGND_13") (pintype "bidirectional"))
      (node (ref "IC6") (pin "8") (pinfunction "AGND_8") (pintype "bidirectional"))
      (node (ref "R12") (pin "1") (pinfunction "1_1") (pintype "passive"))
      (node (ref "R16") (pin "1") (pinfunction "1_1") (pintype "passive"))
      (node (ref "R19") (pin "1") (pinfunction "1_1") (pintype "passive"))
      (node (ref "R2") (pin "1") (pinfunction "1_1") (pintype "passive"))
      (node (ref "R23") (pin "1") (pinfunction "1_1") (pintype "passive"))
      (node (ref "R26") (pin "1") (pinfunction "1_1") (pintype "passive"))
      (node (ref "R30") (pin "1") (pinfunction "1_1") (pintype "passive"))
      (node (ref "R33") (pin "1") (pinfunction "1_1") (pintype "passive"))
      (node (ref "R36") (pin "1") (pinfunction "1_1") (pintype "passive"))
      (node (ref "R38") (pin "1") (pinfunction "1_1") (pintype "passive"))
      (node (ref "R39") (pin "1") (pinfunction "1_1") (pintype "passive"))
      (node (ref "R5") (pin "1") (pinfunction "1_1") (pintype "passive"))
      (node (ref "R9") (pin "1") (pinfunction "1_1") (pintype "passive"))
      (node (ref "X1") (pin "1") (pinfunction "S_1") (pintype "passive"))
      (node (ref "X10") (pin "GND") (pinfunction "GND_GND") (pintype "bidirectional"))
      (node (ref "X10") (pin "GND@1") (pinfunction "GND_GND@1") (pintype "bidirectional"))
      (node (ref "X10") (pin "GND@10") (pinfunction "GND_GND@10") (pintype "bidirectional"))
      (node (ref "X10") (pin "GND@11") (pinfunction "GND_GND@11") (pintype "bidirectional"))
      (node (ref "X10") (pin "GND@12") (pinfunction "GND_GND@12") (pintype "bidirectional"))
      (node (ref "X10") (pin "GND@13") (pinfunction "GND_GND@13") (pintype "bidirectional"))
      (node (ref "X10") (pin "GND@2") (pinfunction "GND_GND@2") (pintype "bidirectional"))
      (node (ref "X10") (pin "GND@3") (pinfunction "GND_GND@3") (pintype "bidirectional"))
      (node (ref "X10") (pin "GND@4") (pinfunction "GND_GND@4") (pintype "bidirectional"))
      (node (ref "X10") (pin "GND@5") (pinfunction "GND_GND@5") (pintype "bidirectional"))
      (node (ref "X10") (pin "GND@6") (pinfunction "GND_GND@6") (pintype "bidirectional"))
      (node (ref "X10") (pin "GND@7") (pinfunction "GND_GND@7") (pintype "bidirectional"))
      (node (ref "X10") (pin "GND@8") (pinfunction "GND_GND@8") (pintype "bidirectional"))
      (node (ref "X10") (pin "GND@9") (pinfunction "GND_GND@9") (pintype "bidirectional"))
      (node (ref "X11") (pin "1") (pinfunction "S_1") (pintype "passive"))
      (node (ref "X12") (pin "1") (pinfunction "S_1") (pintype "passive"))
      (node (ref "X13") (pin "1") (pinfunction "S_1") (pintype "passive"))
      (node (ref "X14") (pin "1") (pinfunction "S_1") (pintype "passive"))
      (node (ref "X15") (pin "1") (pinfunction "S_1") (pintype "passive"))
      (node (ref "X2") (pin "1") (pinfunction "S_1") (pintype "passive"))
      (node (ref "X3") (pin "1") (pinfunction "S_1") (pintype "passive"))
      (node (ref "X4") (pin "1") (pinfunction "S_1") (pintype "passive"))
      (node (ref "X5") (pin "1") (pinfunction "S_1") (pintype "passive"))
      (node (ref "X6") (pin "1") (pinfunction "S_1") (pintype "passive"))
      (node (ref "X7") (pin "1") (pinfunction "S_1") (pintype "passive"))
      (node (ref "X8") (pin "2") (pinfunction "S_2") (pintype "passive"))
      (node (ref "X9") (pin "2") (pinfunction "S_2") (pintype "passive"))
    )
    (net (code "61") (name "Net-(D4-PadC)") (class "Default")
      (node (ref "D4") (pin "C") (pinfunction "C_C") (pintype "passive"))
      (node (ref "R39") (pin "2") (pinfunction "2_2") (pintype "passive"))
    )
    (net (code "62") (name "Net-(IC1-ENU)") (class "Default")
      (node (ref "IC1") (pin "12") (pinfunction "ENW_12") (pintype "bidirectional"))
      (node (ref "IC1") (pin "16") (pinfunction "ENV_16") (pintype "bidirectional"))
      (node (ref "IC1") (pin "2") (pinfunction "ENU_2") (pintype "bidirectional"))
      (node (ref "R1") (pin "2") (pinfunction "2_2") (pintype "passive"))
      (node (ref "R2") (pin "2") (pinfunction "2_2") (pintype "passive"))
    )
    (net (code "63") (name "Net-(IC1-OUTU)") (class "Default")
      (node (ref "IC1") (pin "3") (pinfunction "OUTU_3") (pintype "bidirectional"))
      (node (ref "J1") (pin "1") (pinfunction "1_1") (pintype "passive"))
    )
    (net (code "64") (name "Net-(IC1-OUTV)") (class "Default")
      (node (ref "IC1") (pin "7") (pinfunction "OUTV_7") (pintype "bidirectional"))
      (node (ref "J1") (pin "2") (pinfunction "2_2") (pintype "passive"))
    )
    (net (code "65") (name "Net-(IC1-OUTW)") (class "Default")
      (node (ref "IC1") (pin "10") (pinfunction "OUTW_10") (pintype "bidirectional"))
      (node (ref "J1") (pin "3") (pinfunction "3_3") (pintype "passive"))
    )
    (net (code "66") (name "Net-(IC1-SENSEU)") (class "Default")
      (node (ref "IC1") (pin "4") (pinfunction "SENSEU_4") (pintype "bidirectional"))
      (node (ref "IC1") (pin "8") (pinfunction "SENSEV_8") (pintype "bidirectional"))
      (node (ref "IC1") (pin "9") (pinfunction "SENSEW_9") (pintype "bidirectional"))
      (node (ref "R5") (pin "2") (pinfunction "2_2") (pintype "passive"))
      (node (ref "R6") (pin "1") (pinfunction "1_1") (pintype "passive"))
    )
    (net (code "67") (name "Net-(IC1-STBY{slash}RESET)") (class "Default")
      (node (ref "C1") (pin "2") (pinfunction "2_2") (pintype "passive"))
      (node (ref "IC1") (pin "14") (pinfunction "STBY/RESET_14") (pintype "bidirectional"))
      (node (ref "R3") (pin "1") (pinfunction "1_1") (pintype "passive"))
    )
    (net (code "68") (name "Net-(IC2-ENU)") (class "Default")
      (node (ref "IC2") (pin "12") (pinfunction "ENW_12") (pintype "bidirectional"))
      (node (ref "IC2") (pin "16") (pinfunction "ENV_16") (pintype "bidirectional"))
      (node (ref "IC2") (pin "2") (pinfunction "ENU_2") (pintype "bidirectional"))
      (node (ref "R8") (pin "2") (pinfunction "2_2") (pintype "passive"))
      (node (ref "R9") (pin "2") (pinfunction "2_2") (pintype "passive"))
    )
    (net (code "69") (name "Net-(IC2-OUTU)") (class "Default")
      (node (ref "IC2") (pin "3") (pinfunction "OUTU_3") (pintype "bidirectional"))
      (node (ref "J2") (pin "1") (pinfunction "1_1") (pintype "passive"))
    )
    (net (code "70") (name "Net-(IC2-OUTV)") (class "Default")
      (node (ref "IC2") (pin "7") (pinfunction "OUTV_7") (pintype "bidirectional"))
      (node (ref "J2") (pin "2") (pinfunction "2_2") (pintype "passive"))
    )
    (net (code "71") (name "Net-(IC2-OUTW)") (class "Default")
      (node (ref "IC2") (pin "10") (pinfunction "OUTW_10") (pintype "bidirectional"))
      (node (ref "J2") (pin "3") (pinfunction "3_3") (pintype "passive"))
    )
    (net (code "72") (name "Net-(IC2-SENSEU)") (class "Default")
      (node (ref "IC2") (pin "4") (pinfunction "SENSEU_4") (pintype "bidirectional"))
      (node (ref "IC2") (pin "8") (pinfunction "SENSEV_8") (pintype "bidirectional"))
      (node (ref "IC2") (pin "9") (pinfunction "SENSEW_9") (pintype "bidirectional"))
      (node (ref "R12") (pin "2") (pinfunction "2_2") (pintype "passive"))
      (node (ref "R13") (pin "1") (pinfunction "1_1") (pintype "passive"))
    )
    (net (code "73") (name "Net-(IC2-STBY{slash}RESET)") (class "Default")
      (node (ref "C6") (pin "2") (pinfunction "2_2") (pintype "passive"))
      (node (ref "IC2") (pin "14") (pinfunction "STBY/RESET_14") (pintype "bidirectional"))
      (node (ref "R10") (pin "1") (pinfunction "1_1") (pintype "passive"))
    )
    (net (code "74") (name "Net-(IC3-ENU)") (class "Default")
      (node (ref "IC3") (pin "12") (pinfunction "ENW_12") (pintype "bidirectional"))
      (node (ref "IC3") (pin "16") (pinfunction "ENV_16") (pintype "bidirectional"))
      (node (ref "IC3") (pin "2") (pinfunction "ENU_2") (pintype "bidirectional"))
      (node (ref "R15") (pin "2") (pinfunction "2_2") (pintype "passive"))
      (node (ref "R16") (pin "2") (pinfunction "2_2") (pintype "passive"))
    )
    (net (code "75") (name "Net-(IC3-OUTU)") (class "Default")
      (node (ref "IC3") (pin "3") (pinfunction "OUTU_3") (pintype "bidirectional"))
      (node (ref "J3") (pin "1") (pinfunction "1_1") (pintype "passive"))
    )
    (net (code "76") (name "Net-(IC3-OUTV)") (class "Default")
      (node (ref "IC3") (pin "7") (pinfunction "OUTV_7") (pintype "bidirectional"))
      (node (ref "J3") (pin "2") (pinfunction "2_2") (pintype "passive"))
    )
    (net (code "77") (name "Net-(IC3-OUTW)") (class "Default")
      (node (ref "IC3") (pin "10") (pinfunction "OUTW_10") (pintype "bidirectional"))
      (node (ref "J3") (pin "3") (pinfunction "3_3") (pintype "passive"))
    )
    (net (code "78") (name "Net-(IC3-SENSEU)") (class "Default")
      (node (ref "IC3") (pin "4") (pinfunction "SENSEU_4") (pintype "bidirectional"))
      (node (ref "IC3") (pin "8") (pinfunction "SENSEV_8") (pintype "bidirectional"))
      (node (ref "IC3") (pin "9") (pinfunction "SENSEW_9") (pintype "bidirectional"))
      (node (ref "R19") (pin "2") (pinfunction "2_2") (pintype "passive"))
      (node (ref "R20") (pin "1") (pinfunction "1_1") (pintype "passive"))
    )
    (net (code "79") (name "Net-(IC3-STBY{slash}RESET)") (class "Default")
      (node (ref "C11") (pin "2") (pinfunction "2_2") (pintype "passive"))
      (node (ref "IC3") (pin "14") (pinfunction "STBY/RESET_14") (pintype "bidirectional"))
      (node (ref "R17") (pin "1") (pinfunction "1_1") (pintype "passive"))
    )
    (net (code "80") (name "Net-(IC4-ENU)") (class "Default")
      (node (ref "IC4") (pin "12") (pinfunction "ENW_12") (pintype "bidirectional"))
      (node (ref "IC4") (pin "16") (pinfunction "ENV_16") (pintype "bidirectional"))
      (node (ref "IC4") (pin "2") (pinfunction "ENU_2") (pintype "bidirectional"))
      (node (ref "R22") (pin "2") (pinfunction "2_2") (pintype "passive"))
      (node (ref "R23") (pin "2") (pinfunction "2_2") (pintype "passive"))
    )
    (net (code "81") (name "Net-(IC4-OUTU)") (class "Default")
      (node (ref "IC4") (pin "3") (pinfunction "OUTU_3") (pintype "bidirectional"))
      (node (ref "J4") (pin "1") (pinfunction "1_1") (pintype "passive"))
    )
    (net (code "82") (name "Net-(IC4-OUTV)") (class "Default")
      (node (ref "IC4") (pin "7") (pinfunction "OUTV_7") (pintype "bidirectional"))
      (node (ref "J4") (pin "2") (pinfunction "2_2") (pintype "passive"))
    )
    (net (code "83") (name "Net-(IC4-OUTW)") (class "Default")
      (node (ref "IC4") (pin "10") (pinfunction "OUTW_10") (pintype "bidirectional"))
      (node (ref "J4") (pin "3") (pinfunction "3_3") (pintype "passive"))
    )
    (net (code "84") (name "Net-(IC4-SENSEU)") (class "Default")
      (node (ref "IC4") (pin "4") (pinfunction "SENSEU_4") (pintype "bidirectional"))
      (node (ref "IC4") (pin "8") (pinfunction "SENSEV_8") (pintype "bidirectional"))
      (node (ref "IC4") (pin "9") (pinfunction "SENSEW_9") (pintype "bidirectional"))
      (node (ref "R26") (pin "2") (pinfunction "2_2") (pintype "passive"))
      (node (ref "R27") (pin "1") (pinfunction "1_1") (pintype "passive"))
    )
    (net (code "85") (name "Net-(IC4-STBY{slash}RESET)") (class "Default")
      (node (ref "C16") (pin "2") (pinfunction "2_2") (pintype "passive"))
      (node (ref "IC4") (pin "14") (pinfunction "STBY/RESET_14") (pintype "bidirectional"))
      (node (ref "R24") (pin "1") (pinfunction "1_1") (pintype "passive"))
    )
    (net (code "86") (name "Net-(IC5-ENU)") (class "Default")
      (node (ref "IC5") (pin "12") (pinfunction "ENW_12") (pintype "bidirectional"))
      (node (ref "IC5") (pin "16") (pinfunction "ENV_16") (pintype "bidirectional"))
      (node (ref "IC5") (pin "2") (pinfunction "ENU_2") (pintype "bidirectional"))
      (node (ref "R29") (pin "2") (pinfunction "2_2") (pintype "passive"))
      (node (ref "R30") (pin "2") (pinfunction "2_2") (pintype "passive"))
    )
    (net (code "87") (name "Net-(IC5-OUTU)") (class "Default")
      (node (ref "IC5") (pin "3") (pinfunction "OUTU_3") (pintype "bidirectional"))
      (node (ref "J5") (pin "1") (pinfunction "1_1") (pintype "passive"))
    )
    (net (code "88") (name "Net-(IC5-OUTV)") (class "Default")
      (node (ref "IC5") (pin "7") (pinfunction "OUTV_7") (pintype "bidirectional"))
      (node (ref "J5") (pin "2") (pinfunction "2_2") (pintype "passive"))
    )
    (net (code "89") (name "Net-(IC5-OUTW)") (class "Default")
      (node (ref "IC5") (pin "10") (pinfunction "OUTW_10") (pintype "bidirectional"))
      (node (ref "J5") (pin "3") (pinfunction "3_3") (pintype "passive"))
    )
    (net (code "90") (name "Net-(IC5-SENSEU)") (class "Default")
      (node (ref "IC5") (pin "4") (pinfunction "SENSEU_4") (pintype "bidirectional"))
      (node (ref "IC5") (pin "8") (pinfunction "SENSEV_8") (pintype "bidirectional"))
      (node (ref "IC5") (pin "9") (pinfunction "SENSEW_9") (pintype "bidirectional"))
      (node (ref "R33") (pin "2") (pinfunction "2_2") (pintype "passive"))
      (node (ref "R34") (pin "1") (pinfunction "1_1") (pintype "passive"))
    )
    (net (code "91") (name "Net-(IC5-STBY{slash}RESET)") (class "Default")
      (node (ref "C21") (pin "2") (pinfunction "2_2") (pintype "passive"))
      (node (ref "IC5") (pin "14") (pinfunction "STBY/RESET_14") (pintype "bidirectional"))
      (node (ref "R31") (pin "1") (pinfunction "1_1") (pintype "passive"))
    )
    (net (code "92") (name "Net-(IC6-BOOT)") (class "Default")
      (node (ref "C31") (pin "1") (pinfunction "1_1") (pintype "passive"))
      (node (ref "IC6") (pin "4") (pinfunction "BOOT_4") (pintype "bidirectional"))
    )
    (net (code "93") (name "Net-(IC6-EN)") (class "Default")
      (node (ref "C26") (pin "1") (pinfunction "1_1") (pintype "passive"))
      (node (ref "C29") (pin "1") (pinfunction "1_1") (pintype "passive"))
      (node (ref "C30") (pin "1") (pinfunction "1_1") (pintype "passive"))
      (node (ref "D1") (pin "C") (pinfunction "C_C") (pintype "passive"))
      (node (ref "D2") (pin "C") (pinfunction "C_C") (pintype "passive"))
      (node (ref "D3") (pin "C") (pinfunction "C_C") (pintype "passive"))
      (node (ref "IC6") (pin "10") (pinfunction "VIN_1_10") (pintype "bidirectional"))
      (node (ref "IC6") (pin "11") (pinfunction "VIN_2_11") (pintype "bidirectional"))
      (node (ref "IC6") (pin "12") (pinfunction "VIN_3_12") (pintype "bidirectional"))
      (node (ref "IC6") (pin "9") (pinfunction "EN_9") (pintype "bidirectional"))
    )
    (net (code "94") (name "Net-(IC6-FB)") (class "Default")
      (node (ref "IC6") (pin "7") (pinfunction "FB_7") (pintype "bidirectional"))
      (node (ref "R37") (pin "1") (pinfunction "1_1") (pintype "passive"))
      (node (ref "R38") (pin "2") (pinfunction "2_2") (pintype "passive"))
    )
    (net (code "95") (name "Net-(IC6-RT)") (class "Default")
      (node (ref "IC6") (pin "6") (pinfunction "RT_6") (pintype "bidirectional"))
      (node (ref "R36") (pin "2") (pinfunction "2_2") (pintype "passive"))
    )
    (net (code "96") (name "Net-(IC6-SW_1)") (class "Default")
      (node (ref "C31") (pin "2") (pinfunction "2_2") (pintype "passive"))
      (node (ref "IC6") (pin "1") (pinfunction "SW_1_1") (pintype "bidirectional"))
      (node (ref "IC6") (pin "2") (pinfunction "SW_2_2") (pintype "bidirectional"))
      (node (ref "IC6") (pin "3") (pinfunction "SW_3_3") (pintype "bidirectional"))
      (node (ref "L1") (pin "1") (pinfunction "1_1") (pintype "bidirectional"))
    )
    (net (code "97") (name "Net-(X8A-S)") (class "Default")
      (node (ref "D2") (pin "A") (pinfunction "A_A") (pintype "passive"))
      (node (ref "X8") (pin "1") (pinfunction "S_1") (pintype "passive"))
    )
    (net (code "98") (name "Net-(X9A-S)") (class "Default")
      (node (ref "D3") (pin "A") (pinfunction "A_A") (pintype "passive"))
      (node (ref "X9") (pin "1") (pinfunction "S_1") (pintype "passive"))
    )
    (net (code "99") (name "Net-(X10-~{RESET}-Pad!RESET)") (class "Default")
      (node (ref "X10") (pin "!RESET") (pinfunction "~{RESET}_!RESET") (pintype "bidirectional"))
      (node (ref "X10") (pin "RESET") (pinfunction "~{RESET}_RESET") (pintype "bidirectional"))
    )
    (net (code "100") (name "unconnected-(IC6-PG-Pad5)") (class "Default")
      (node (ref "IC6") (pin "5") (pinfunction "PG_5") (pintype "bidirectional"))
    )
    (net (code "101") (name "unconnected-(X10-Pad23)") (class "Default")
      (node (ref "X10") (pin "23") (pinfunction "23_23") (pintype "bidirectional"))
    )
    (net (code "102") (name "unconnected-(X10-Pad24)") (class "Default")
      (node (ref "X10") (pin "24") (pinfunction "24_24") (pintype "bidirectional"))
    )
    (net (code "103") (name "unconnected-(X10-Pad25)") (class "Default")
      (node (ref "X10") (pin "25") (pinfunction "25_25") (pintype "bidirectional"))
    )
    (net (code "104") (name "unconnected-(X10-Pad26)") (class "Default")
      (node (ref "X10") (pin "26") (pinfunction "26_26") (pintype "bidirectional"))
    )
    (net (code "105") (name "unconnected-(X10-Pad27)") (class "Default")
      (node (ref "X10") (pin "27") (pinfunction "27_27") (pintype "bidirectional"))
    )
    (net (code "106") (name "unconnected-(X10-Pad28)") (class "Default")
      (node (ref "X10") (pin "28") (pinfunction "28_28") (pintype "bidirectional"))
    )
    (net (code "107") (name "unconnected-(X10-Pad29)") (class "Default")
      (node (ref "X10") (pin "29") (pinfunction "29_29") (pintype "bidirectional"))
    )
    (net (code "108") (name "unconnected-(X10-Pad30)") (class "Default")
      (node (ref "X10") (pin "30") (pinfunction "30_30") (pintype "bidirectional"))
    )
    (net (code "109") (name "unconnected-(X10-Pad31)") (class "Default")
      (node (ref "X10") (pin "31") (pinfunction "31_31") (pintype "bidirectional"))
    )
    (net (code "110") (name "unconnected-(X10-Pad32)") (class "Default")
      (node (ref "X10") (pin "32") (pinfunction "32_32") (pintype "bidirectional"))
    )
    (net (code "111") (name "unconnected-(X10-Pad33)") (class "Default")
      (node (ref "X10") (pin "33") (pinfunction "33_33") (pintype "bidirectional"))
    )
    (net (code "112") (name "unconnected-(X10-Pad34)") (class "Default")
      (node (ref "X10") (pin "34") (pinfunction "34_34") (pintype "bidirectional"))
    )
    (net (code "113") (name "unconnected-(X10-Pad35)") (class "Default")
      (node (ref "X10") (pin "35") (pinfunction "35_35") (pintype "bidirectional"))
    )
    (net (code "114") (name "unconnected-(X10-Pad36)") (class "Default")
      (node (ref "X10") (pin "36") (pinfunction "36_36") (pintype "bidirectional"))
    )
    (net (code "115") (name "unconnected-(X10-Pad37)") (class "Default")
      (node (ref "X10") (pin "37") (pinfunction "37_37") (pintype "bidirectional"))
    )
    (net (code "116") (name "unconnected-(X10-Pad38)") (class "Default")
      (node (ref "X10") (pin "38") (pinfunction "38_38") (pintype "bidirectional"))
    )
    (net (code "117") (name "unconnected-(X10-Pad39)") (class "Default")
      (node (ref "X10") (pin "39") (pinfunction "39_39") (pintype "bidirectional"))
    )
    (net (code "118") (name "unconnected-(X10-Pad41)") (class "Default")
      (node (ref "X10") (pin "41") (pinfunction "41_41") (pintype "bidirectional"))
    )
    (net (code "119") (name "unconnected-(X10-Pad42)") (class "Default")
      (node (ref "X10") (pin "42") (pinfunction "42_42") (pintype "bidirectional"))
    )
    (net (code "120") (name "unconnected-(X10-Pad43)") (class "Default")
      (node (ref "X10") (pin "43") (pinfunction "43_43") (pintype "bidirectional"))
    )
    (net (code "121") (name "unconnected-(X10-Pad44)") (class "Default")
      (node (ref "X10") (pin "44") (pinfunction "44_44") (pintype "bidirectional"))
    )
    (net (code "122") (name "unconnected-(X10-Pad45)") (class "Default")
      (node (ref "X10") (pin "45") (pinfunction "45_45") (pintype "bidirectional"))
    )
    (net (code "123") (name "unconnected-(X10-Pad46)") (class "Default")
      (node (ref "X10") (pin "46") (pinfunction "46_46") (pintype "bidirectional"))
    )
    (net (code "124") (name "unconnected-(X10-Pad47)") (class "Default")
      (node (ref "X10") (pin "47") (pinfunction "47_47") (pintype "bidirectional"))
    )
    (net (code "125") (name "unconnected-(X10-Pad49)") (class "Default")
      (node (ref "X10") (pin "49") (pinfunction "49_49") (pintype "bidirectional"))
    )
    (net (code "126") (name "unconnected-(X10-Pad50)") (class "Default")
      (node (ref "X10") (pin "50") (pinfunction "50_50") (pintype "bidirectional"))
    )
    (net (code "127") (name "unconnected-(X10-Pad55)") (class "Default")
      (node (ref "X10") (pin "55") (pinfunction "55_55") (pintype "bidirectional"))
    )
    (net (code "128") (name "unconnected-(X10-Pad63)") (class "Default")
      (node (ref "X10") (pin "63") (pinfunction "63_63") (pintype "bidirectional"))
    )
    (net (code "129") (name "unconnected-(X10-Pad68)") (class "Default")
      (node (ref "X10") (pin "68") (pinfunction "68_68") (pintype "bidirectional"))
    )
    (net (code "130") (name "unconnected-(X10-Pad69)") (class "Default")
      (node (ref "X10") (pin "69") (pinfunction "69_69") (pintype "bidirectional"))
    )
    (net (code "131") (name "unconnected-(X10-Pad70)") (class "Default")
      (node (ref "X10") (pin "70") (pinfunction "70_70") (pintype "bidirectional"))
    )
    (net (code "132") (name "unconnected-(X10-Pad71)") (class "Default")
      (node (ref "X10") (pin "71") (pinfunction "71_71") (pintype "bidirectional"))
    )
    (net (code "133") (name "unconnected-(X10-Pad72)") (class "Default")
      (node (ref "X10") (pin "72") (pinfunction "72_72") (pintype "bidirectional"))
    )
    (net (code "134") (name "unconnected-(X10-Pad73)") (class "Default")
      (node (ref "X10") (pin "73") (pinfunction "73_73") (pintype "bidirectional"))
    )
    (net (code "135") (name "unconnected-(X10-Pad74)") (class "Default")
      (node (ref "X10") (pin "74") (pinfunction "74_74") (pintype "bidirectional"))
    )
    (net (code "136") (name "unconnected-(X10-Pad75)") (class "Default")
      (node (ref "X10") (pin "75") (pinfunction "75_75") (pintype "bidirectional"))
    )
    (net (code "137") (name "unconnected-(X10-Pad85)") (class "Default")
      (node (ref "X10") (pin "85") (pinfunction "85_85") (pintype "bidirectional"))
    )
    (net (code "138") (name "unconnected-(X10-PadA8)") (class "Default")
      (node (ref "X10") (pin "A8") (pinfunction "A8_A8") (pintype "bidirectional"))
    )
    (net (code "139") (name "unconnected-(X10-PadA9)") (class "Default")
      (node (ref "X10") (pin "A9") (pinfunction "A9_A9") (pintype "bidirectional"))
    )
    (net (code "140") (name "unconnected-(X10-PadA10)") (class "Default")
      (node (ref "X10") (pin "A10") (pinfunction "A10_A10") (pintype "bidirectional"))
    )
    (net (code "141") (name "unconnected-(X10-PadA11)") (class "Default")
      (node (ref "X10") (pin "A11") (pinfunction "A11_A11") (pintype "bidirectional"))
    )
    (net (code "142") (name "unconnected-(X10-PadAREF)") (class "Default")
      (node (ref "X10") (pin "AREF") (pinfunction "AREF_AREF") (pintype "bidirectional"))
    )
    (net (code "143") (name "unconnected-(X10-PadCKN)") (class "Default")
      (node (ref "X10") (pin "CKN") (pinfunction "CKN_CKN") (pintype "bidirectional"))
    )
    (net (code "144") (name "unconnected-(X10-PadCKP)") (class "Default")
      (node (ref "X10") (pin "CKP") (pinfunction "CKP_CKP") (pintype "bidirectional"))
    )
    (net (code "145") (name "unconnected-(X10-PadD0N)") (class "Default")
      (node (ref "X10") (pin "D0N") (pinfunction "D0N_D0N") (pintype "bidirectional"))
    )
    (net (code "146") (name "unconnected-(X10-PadD0P)") (class "Default")
      (node (ref "X10") (pin "D0P") (pinfunction "D0P_D0P") (pintype "bidirectional"))
    )
    (net (code "147") (name "unconnected-(X10-PadD1N)") (class "Default")
      (node (ref "X10") (pin "D1N") (pinfunction "D1N_D1N") (pintype "bidirectional"))
    )
    (net (code "148") (name "unconnected-(X10-PadD1P)") (class "Default")
      (node (ref "X10") (pin "D1P") (pinfunction "D1P_D1P") (pintype "bidirectional"))
    )
    (net (code "149") (name "unconnected-(X10-PadIOREF)") (class "Default")
      (node (ref "X10") (pin "IOREF") (pinfunction "IOREF_IOREF") (pintype "bidirectional"))
    )
  )
)
